# MCU_Board_V1_1_0.net
KiCad netlist of a schematic drawn in EAGLE
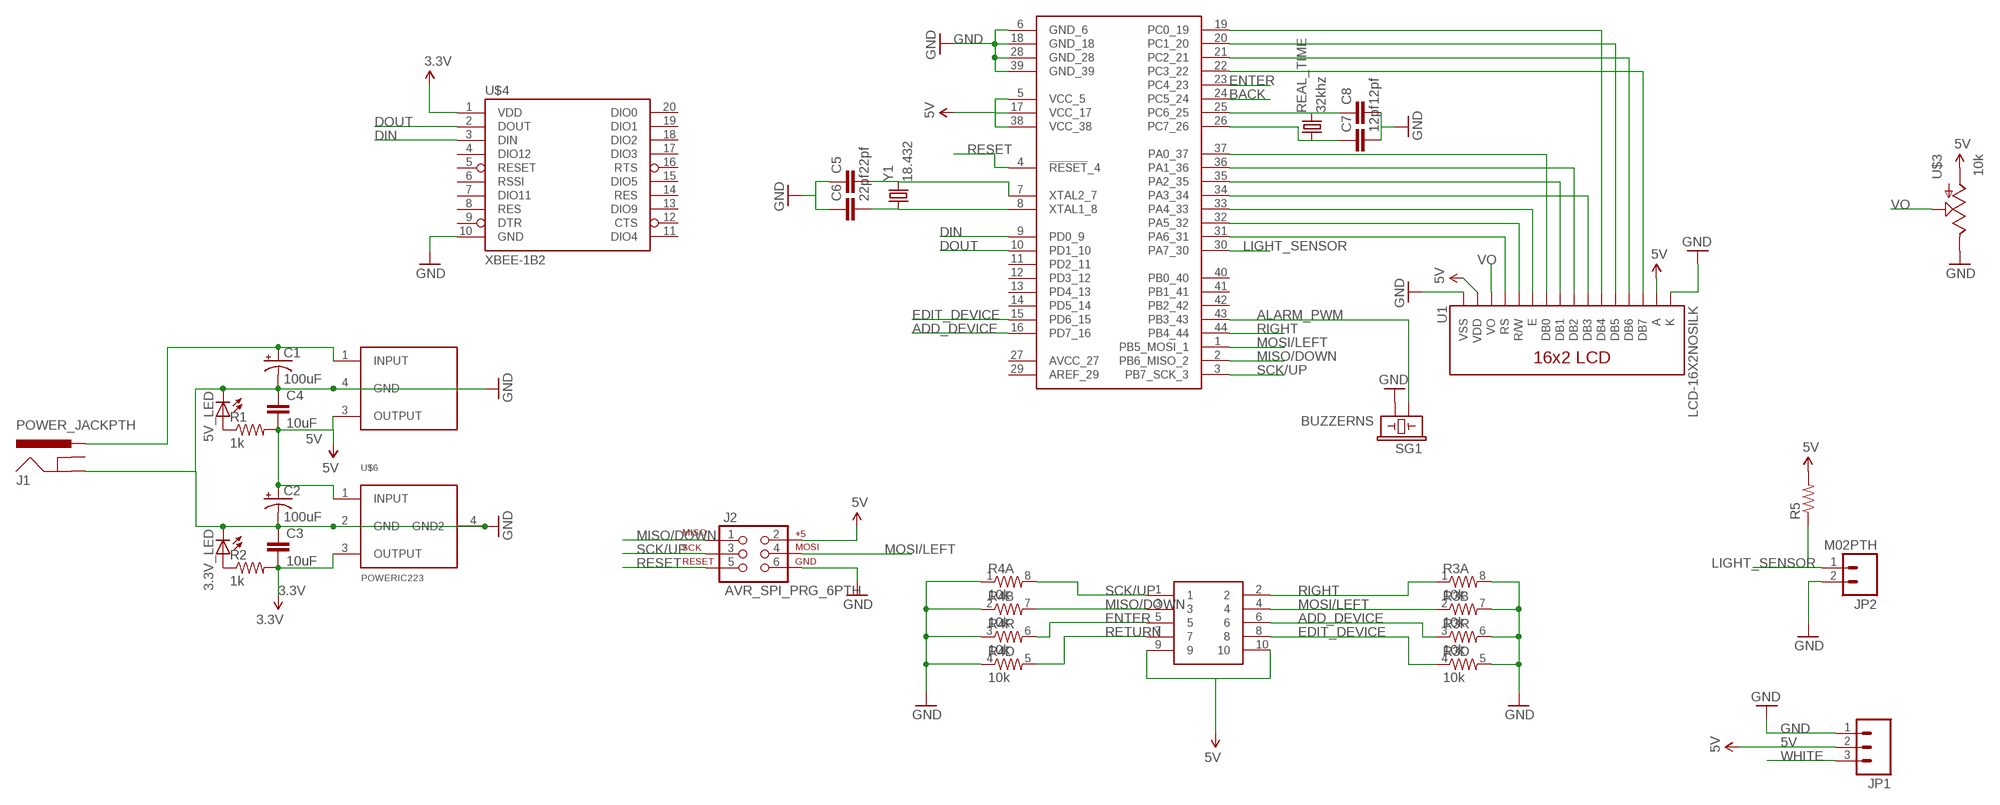
[diagram p0: schematic, sheet 1]

(export (version "E")
  (design (tool "Eeschema 10.0.6"))
  (components
    (comp (ref "3.3V_LED")
      (value "LED1206")
      (footprint "eagle-import:LED-1206")
      (libsource (lib "eagle-import") (part "LED1206"))
    )
    (comp (ref "5V_LED")
      (value "LED1206")
      (footprint "eagle-import:LED-1206")
      (libsource (lib "eagle-import") (part "LED1206"))
    )
    (comp (ref "C1")
      (value "100uF")
      (footprint "eagle-import:PANASONIC_D")
      (libsource (lib "eagle-import") (part "CAP_POLD"))
    )
    (comp (ref "C2")
      (value "100uF")
      (footprint "eagle-import:PANASONIC_D")
      (libsource (lib "eagle-import") (part "CAP_POLD"))
    )
    (comp (ref "C3")
      (value "10uF")
      (footprint "eagle-import:1206")
      (libsource (lib "eagle-import") (part "CAP1206"))
    )
    (comp (ref "C4")
      (value "10uF")
      (footprint "eagle-import:1206")
      (libsource (lib "eagle-import") (part "CAP1206"))
    )
    (comp (ref "C5")
      (value "22pf")
      (footprint "eagle-import:0805")
      (libsource (lib "eagle-import") (part "CAP0805"))
    )
    (comp (ref "C6")
      (value "22pf")
      (footprint "eagle-import:0805")
      (libsource (lib "eagle-import") (part "CAP0805"))
    )
    (comp (ref "C7")
      (value "12pf")
      (footprint "eagle-import:0805")
      (libsource (lib "eagle-import") (part "SparkFun-Passives_CAP0805"))
    )
    (comp (ref "C8")
      (value "12pf")
      (footprint "eagle-import:0805")
      (libsource (lib "eagle-import") (part "SparkFun-Passives_CAP0805"))
    )
    (comp (ref "J1")
      (value "POWER_JACKPTH")
      (footprint "eagle-import:POWER_JACK_PTH")
      (libsource (lib "eagle-import") (part "POWER_JACKPTH"))
    )
    (comp (ref "J2")
      (value "AVR_SPI_PRG_6PTH")
      (footprint "eagle-import:2X3")
      (libsource (lib "eagle-import") (part "AVR_SPI_PRG_6PTH"))
    )
    (comp (ref "JP1")
      (value "M03PTH")
      (footprint "eagle-import:1X03")
      (libsource (lib "eagle-import") (part "M03PTH"))
    )
    (comp (ref "JP2")
      (value "M02PTH")
      (footprint "eagle-import:1X02")
      (libsource (lib "eagle-import") (part "M02PTH"))
    )
    (comp (ref "R1")
      (value "1k")
      (footprint "eagle-import:1206")
      (libsource (lib "eagle-import") (part "RESISTOR1206"))
    )
    (comp (ref "R2")
      (value "1k")
      (footprint "eagle-import:1206")
      (libsource (lib "eagle-import") (part "RESISTOR1206"))
    )
    (comp (ref "R3")
      (value "10k")
      (footprint "eagle-import:0603-ARV")
      (libsource (lib "eagle-import") (part "RESISTOR-ARRAY0603-ARV"))
    )
    (comp (ref "R4")
      (value "10k")
      (footprint "eagle-import:0603-ARV")
      (libsource (lib "eagle-import") (part "RESISTOR-ARRAY0603-ARV"))
    )
    (comp (ref "R5")
      (value "RESISTOR1206")
      (footprint "eagle-import:1206")
      (libsource (lib "eagle-import") (part "RESISTOR1206"))
    )
    (comp (ref "REAL_TIME")
      (value "32khz")
      (footprint "eagle-import:TC26H")
      (libsource (lib "eagle-import") (part "CRYSTALTC26H"))
    )
    (comp (ref "SG1")
      (value "BUZZERNS")
      (footprint "eagle-import:BUZZER-12MM-NS")
      (libsource (lib "eagle-import") (part "BUZZERNS"))
    )
    (comp (ref "U$1")
      (value "ATMEGA1284")
      (footprint "eagle-import:TQFP44")
      (libsource (lib "eagle-import") (part "ATMEGA1284"))
    )
    (comp (ref "U$2")
      (value "10PIN_HEADER_MALETHROUGH-HOLE")
      (footprint "eagle-import:2X5-SHROUDED")
      (libsource (lib "eagle-import") (part "10PIN_HEADER_MALETHROUGH-HOLE"))
    )
    (comp (ref "U$3")
      (value "10k")
      (footprint "eagle-import:TRIM_POT")
      (libsource (lib "eagle-import") (part "POTTRIM"))
    )
    (comp (ref "U$4")
      (value "XBEE-1B2")
      (footprint "eagle-import:XBEE-SILK")
      (libsource (lib "eagle-import") (part "XBEE-1B2"))
    )
    (comp (ref "U$5")
      (value "DPACK_V_REG")
      (footprint "eagle-import:DPAK")
      (libsource (lib "eagle-import") (part "DPACK_V_REG"))
    )
    (comp (ref "U$6")
      (value "POWERIC223")
      (footprint "eagle-import:SOT223")
      (libsource (lib "eagle-import") (part "POWERIC223"))
    )
    (comp (ref "U1")
      (value "LCD-16X2NOSILK")
      (footprint "eagle-import:LCD-16X2_NOSILK")
      (libsource (lib "eagle-import") (part "LCD-16X2NOSILK"))
    )
    (comp (ref "Y1")
      (value "18.432")
      (footprint "eagle-import:HC49US")
      (libsource (lib "eagle-import") (part "CRYSTALHC49US"))
    )
  )
  (nets
    (net (code "1") (name "/ADD_DEVICE") (class "Default")
      (node (ref "R3") (pin "3") (pinfunction "1_3") (pintype "passive"))
      (node (ref "U$1") (pin "16") (pinfunction "PD7_16_16") (pintype "bidirectional"))
      (node (ref "U$2") (pin "6") (pinfunction "6_6") (pintype "bidirectional"))
    )
    (net (code "2") (name "/ALARM_PWM") (class "Default")
      (node (ref "SG1") (pin "+") (pinfunction "1_+") (pintype "passive"))
      (node (ref "U$1") (pin "43") (pinfunction "PB3_43_43") (pintype "bidirectional"))
    )
    (net (code "3") (name "/BACK") (class "Default")
      (node (ref "U$1") (pin "24") (pinfunction "PC5_24_24") (pintype "bidirectional"))
    )
    (net (code "4") (name "/DIN") (class "Default")
      (node (ref "U$1") (pin "9") (pinfunction "PD0_9_9") (pintype "bidirectional"))
      (node (ref "U$4") (pin "3") (pinfunction "DIN_3") (pintype "input"))
    )
    (net (code "5") (name "/DOUT") (class "Default")
      (node (ref "U$1") (pin "10") (pinfunction "PD1_10_10") (pintype "bidirectional"))
      (node (ref "U$4") (pin "2") (pinfunction "DOUT_2") (pintype "output"))
    )
    (net (code "6") (name "/EDIT_DEVICE") (class "Default")
      (node (ref "R3") (pin "4") (pinfunction "1_4") (pintype "passive"))
      (node (ref "U$1") (pin "15") (pinfunction "PD6_15_15") (pintype "bidirectional"))
      (node (ref "U$2") (pin "8") (pinfunction "8_8") (pintype "bidirectional"))
    )
    (net (code "7") (name "/ENTER") (class "Default")
      (node (ref "R4") (pin "6") (pinfunction "2_6") (pintype "passive"))
      (node (ref "U$1") (pin "23") (pinfunction "PC4_23_23") (pintype "bidirectional"))
      (node (ref "U$2") (pin "5") (pinfunction "5_5") (pintype "bidirectional"))
    )
    (net (code "8") (name "/LIGHT_SENSOR") (class "Default")
      (node (ref "JP2") (pin "1") (pinfunction "1_1") (pintype "passive"))
      (node (ref "R5") (pin "1") (pinfunction "1_1") (pintype "passive"))
      (node (ref "U$1") (pin "30") (pinfunction "PA7_30_30") (pintype "bidirectional"))
    )
    (net (code "9") (name "/MISO{slash}DOWN") (class "Default")
      (node (ref "J2") (pin "1") (pinfunction "1_1") (pintype "passive"))
      (node (ref "R4") (pin "7") (pinfunction "2_7") (pintype "passive"))
      (node (ref "U$1") (pin "2") (pinfunction "PB6_MISO_2_2") (pintype "bidirectional"))
      (node (ref "U$2") (pin "3") (pinfunction "3_3") (pintype "bidirectional"))
    )
    (net (code "10") (name "/MOSI{slash}LEFT") (class "Default")
      (node (ref "J2") (pin "4") (pinfunction "4_4") (pintype "passive"))
      (node (ref "R3") (pin "2") (pinfunction "1_2") (pintype "passive"))
      (node (ref "U$1") (pin "1") (pinfunction "PB5_MOSI_1_1") (pintype "bidirectional"))
      (node (ref "U$2") (pin "4") (pinfunction "4_4") (pintype "bidirectional"))
    )
    (net (code "11") (name "/RESET") (class "Default")
      (node (ref "J2") (pin "5") (pinfunction "5_5") (pintype "passive"))
      (node (ref "U$1") (pin "4") (pinfunction "~{RESET}_4_4") (pintype "bidirectional"))
    )
    (net (code "12") (name "/RETURN") (class "Default")
      (node (ref "R4") (pin "5") (pinfunction "2_5") (pintype "passive"))
      (node (ref "U$2") (pin "7") (pinfunction "7_7") (pintype "bidirectional"))
    )
    (net (code "13") (name "/RIGHT") (class "Default")
      (node (ref "R3") (pin "1") (pinfunction "1_1") (pintype "passive"))
      (node (ref "U$1") (pin "44") (pinfunction "PB4_44_44") (pintype "bidirectional"))
      (node (ref "U$2") (pin "2") (pinfunction "2_2") (pintype "bidirectional"))
    )
    (net (code "14") (name "/SCK{slash}UP") (class "Default")
      (node (ref "J2") (pin "3") (pinfunction "3_3") (pintype "passive"))
      (node (ref "R4") (pin "8") (pinfunction "2_8") (pintype "passive"))
      (node (ref "U$1") (pin "3") (pinfunction "PB7_SCK_3_3") (pintype "bidirectional"))
      (node (ref "U$2") (pin "1") (pinfunction "1_1") (pintype "bidirectional"))
    )
    (net (code "15") (name "/VO") (class "Default")
      (node (ref "U$3") (pin "1") (pinfunction "S_1") (pintype "passive"))
      (node (ref "U1") (pin "3") (pinfunction "VO_3") (pintype "bidirectional"))
    )
    (net (code "16") (name "/WHITE") (class "Default")
      (node (ref "JP1") (pin "3") (pinfunction "3_3") (pintype "passive"))
    )
    (net (code "17") (name "3.3V") (class "Default")
      (node (ref "C3") (pin "2") (pinfunction "2_2") (pintype "passive"))
      (node (ref "R2") (pin "2") (pinfunction "2_2") (pintype "passive"))
      (node (ref "U$4") (pin "1") (pinfunction "VDD_1") (pintype "power_in"))
      (node (ref "U$6") (pin "3") (pinfunction "OUTPUT_3") (pintype "bidirectional"))
    )
    (net (code "18") (name "5V") (class "Default")
      (node (ref "C2") (pin "+") (pinfunction "+_+") (pintype "passive"))
      (node (ref "C4") (pin "2") (pinfunction "2_2") (pintype "passive"))
      (node (ref "J2") (pin "2") (pinfunction "2_2") (pintype "passive"))
      (node (ref "JP1") (pin "2") (pinfunction "2_2") (pintype "passive"))
      (node (ref "R1") (pin "2") (pinfunction "2_2") (pintype "passive"))
      (node (ref "R5") (pin "2") (pinfunction "2_2") (pintype "passive"))
      (node (ref "U$1") (pin "17") (pinfunction "VCC_17_17") (pintype "bidirectional"))
      (node (ref "U$1") (pin "38") (pinfunction "VCC_38_38") (pintype "bidirectional"))
      (node (ref "U$1") (pin "5") (pinfunction "VCC_5_5") (pintype "bidirectional"))
      (node (ref "U$2") (pin "10") (pinfunction "10_10") (pintype "bidirectional"))
      (node (ref "U$2") (pin "9") (pinfunction "9_9") (pintype "bidirectional"))
      (node (ref "U$3") (pin "3") (pinfunction "A_3") (pintype "passive"))
      (node (ref "U$5") (pin "3") (pinfunction "OUTPUT_3") (pintype "bidirectional"))
      (node (ref "U$6") (pin "1") (pinfunction "INPUT_1") (pintype "bidirectional"))
      (node (ref "U1") (pin "15") (pinfunction "A_15") (pintype "power_in"))
      (node (ref "U1") (pin "2") (pinfunction "VDD_2") (pintype "power_in"))
    )
    (net (code "19") (name "GND") (class "Default")
      (node (ref "3.3V_LED") (pin "C") (pinfunction "C_C") (pintype "passive"))
      (node (ref "5V_LED") (pin "C") (pinfunction "C_C") (pintype "passive"))
      (node (ref "C1") (pin "-") (pinfunction "-_-") (pintype "passive"))
      (node (ref "C2") (pin "-") (pinfunction "-_-") (pintype "passive"))
      (node (ref "C3") (pin "1") (pinfunction "1_1") (pintype "passive"))
      (node (ref "C4") (pin "1") (pinfunction "1_1") (pintype "passive"))
      (node (ref "C5") (pin "1") (pinfunction "1_1") (pintype "passive"))
      (node (ref "C6") (pin "1") (pinfunction "1_1") (pintype "passive"))
      (node (ref "C7") (pin "2") (pinfunction "2_2") (pintype "passive"))
      (node (ref "C8") (pin "2") (pinfunction "2_2") (pintype "passive"))
      (node (ref "J1") (pin "GND") (pinfunction "GND_GND") (pintype "bidirectional"))
      (node (ref "J2") (pin "6") (pinfunction "6_6") (pintype "passive"))
      (node (ref "JP1") (pin "1") (pinfunction "1_1") (pintype "passive"))
      (node (ref "JP2") (pin "2") (pinfunction "2_2") (pintype "passive"))
      (node (ref "R3") (pin "5") (pinfunction "2_5") (pintype "passive"))
      (node (ref "R3") (pin "6") (pinfunction "2_6") (pintype "passive"))
      (node (ref "R3") (pin "7") (pinfunction "2_7") (pintype "passive"))
      (node (ref "R3") (pin "8") (pinfunction "2_8") (pintype "passive"))
      (node (ref "R4") (pin "1") (pinfunction "1_1") (pintype "passive"))
      (node (ref "R4") (pin "2") (pinfunction "1_2") (pintype "passive"))
      (node (ref "R4") (pin "3") (pinfunction "1_3") (pintype "passive"))
      (node (ref "R4") (pin "4") (pinfunction "1_4") (pintype "passive"))
      (node (ref "SG1") (pin "-") (pinfunction "2_-") (pintype "passive"))
      (node (ref "U$1") (pin "18") (pinfunction "GND_18_18") (pintype "bidirectional"))
      (node (ref "U$1") (pin "28") (pinfunction "GND_28_28") (pintype "bidirectional"))
      (node (ref "U$1") (pin "39") (pinfunction "GND_39_39") (pintype "bidirectional"))
      (node (ref "U$1") (pin "6") (pinfunction "GND_6_6") (pintype "bidirectional"))
      (node (ref "U$3") (pin "2") (pinfunction "E_2") (pintype "passive"))
      (node (ref "U$4") (pin "10") (pinfunction "GND_10") (pintype "power_in"))
      (node (ref "U$5") (pin "4") (pinfunction "GND_4") (pintype "bidirectional"))
      (node (ref "U$6") (pin "2") (pinfunction "GND_2") (pintype "bidirectional"))
      (node (ref "U$6") (pin "4") (pinfunction "GND2_4") (pintype "bidirectional"))
      (node (ref "U1") (pin "1") (pinfunction "VSS_1") (pintype "power_in"))
      (node (ref "U1") (pin "16") (pinfunction "K_16") (pintype "power_in"))
    )
    (net (code "20") (name "Net-(3.3V_LED-PadA)") (class "Default")
      (node (ref "3.3V_LED") (pin "A") (pinfunction "A_A") (pintype "passive"))
      (node (ref "R2") (pin "1") (pinfunction "1_1") (pintype "passive"))
    )
    (net (code "21") (name "Net-(5V_LED-PadA)") (class "Default")
      (node (ref "5V_LED") (pin "A") (pinfunction "A_A") (pintype "passive"))
      (node (ref "R1") (pin "1") (pinfunction "1_1") (pintype "passive"))
    )
    (net (code "22") (name "Net-(U$1-PA0_37)") (class "Default")
      (node (ref "U$1") (pin "37") (pinfunction "PA0_37_37") (pintype "bidirectional"))
      (node (ref "U1") (pin "7") (pinfunction "DB0_7") (pintype "bidirectional"))
    )
    (net (code "23") (name "Net-(U$1-PA1_36)") (class "Default")
      (node (ref "U$1") (pin "36") (pinfunction "PA1_36_36") (pintype "bidirectional"))
      (node (ref "U1") (pin "9") (pinfunction "DB2_9") (pintype "bidirectional"))
    )
    (net (code "24") (name "Net-(U$1-PA2_35)") (class "Default")
      (node (ref "U$1") (pin "35") (pinfunction "PA2_35_35") (pintype "bidirectional"))
      (node (ref "U1") (pin "8") (pinfunction "DB1_8") (pintype "bidirectional"))
    )
    (net (code "25") (name "Net-(U$1-PA3_34)") (class "Default")
      (node (ref "U$1") (pin "34") (pinfunction "PA3_34_34") (pintype "bidirectional"))
      (node (ref "U1") (pin "10") (pinfunction "DB3_10") (pintype "bidirectional"))
    )
    (net (code "26") (name "Net-(U$1-PA4_33)") (class "Default")
      (node (ref "U$1") (pin "33") (pinfunction "PA4_33_33") (pintype "bidirectional"))
      (node (ref "U1") (pin "6") (pinfunction "E_6") (pintype "input"))
    )
    (net (code "27") (name "Net-(U$1-PA5_32)") (class "Default")
      (node (ref "U$1") (pin "32") (pinfunction "PA5_32_32") (pintype "bidirectional"))
      (node (ref "U1") (pin "5") (pinfunction "R/W_5") (pintype "input"))
    )
    (net (code "28") (name "Net-(U$1-PA6_31)") (class "Default")
      (node (ref "U$1") (pin "31") (pinfunction "PA6_31_31") (pintype "bidirectional"))
      (node (ref "U1") (pin "4") (pinfunction "RS_4") (pintype "input"))
    )
    (net (code "29") (name "Net-(U$1-PC0_19)") (class "Default")
      (node (ref "U$1") (pin "19") (pinfunction "PC0_19_19") (pintype "bidirectional"))
      (node (ref "U1") (pin "11") (pinfunction "DB4_11") (pintype "bidirectional"))
    )
    (net (code "30") (name "Net-(U$1-PC1_20)") (class "Default")
      (node (ref "U$1") (pin "20") (pinfunction "PC1_20_20") (pintype "bidirectional"))
      (node (ref "U1") (pin "12") (pinfunction "DB5_12") (pintype "bidirectional"))
    )
    (net (code "31") (name "Net-(U$1-PC2_21)") (class "Default")
      (node (ref "U$1") (pin "21") (pinfunction "PC2_21_21") (pintype "bidirectional"))
      (node (ref "U1") (pin "13") (pinfunction "DB6_13") (pintype "bidirectional"))
    )
    (net (code "32") (name "Net-(U$1-PC3_22)") (class "Default")
      (node (ref "U$1") (pin "22") (pinfunction "PC3_22_22") (pintype "bidirectional"))
      (node (ref "U1") (pin "14") (pinfunction "DB7_14") (pintype "bidirectional"))
    )
    (net (code "33") (name "Net-(U$1-PC6_25)") (class "Default")
      (node (ref "C8") (pin "1") (pinfunction "1_1") (pintype "passive"))
      (node (ref "REAL_TIME") (pin "2") (pinfunction "2_2") (pintype "passive"))
      (node (ref "U$1") (pin "25") (pinfunction "PC6_25_25") (pintype "bidirectional"))
    )
    (net (code "34") (name "Net-(U$1-PC7_26)") (class "Default")
      (node (ref "C7") (pin "1") (pinfunction "1_1") (pintype "passive"))
      (node (ref "REAL_TIME") (pin "1") (pinfunction "1_1") (pintype "passive"))
      (node (ref "U$1") (pin "26") (pinfunction "PC7_26_26") (pintype "bidirectional"))
    )
    (net (code "35") (name "Net-(U$1-XTAL1_8)") (class "Default")
      (node (ref "C6") (pin "2") (pinfunction "2_2") (pintype "passive"))
      (node (ref "U$1") (pin "8") (pinfunction "XTAL1_8_8") (pintype "bidirectional"))
      (node (ref "Y1") (pin "1") (pinfunction "1_1") (pintype "passive"))
    )
    (net (code "36") (name "Net-(U$1-XTAL2_7)") (class "Default")
      (node (ref "C5") (pin "2") (pinfunction "2_2") (pintype "passive"))
      (node (ref "U$1") (pin "7") (pinfunction "XTAL2_7_7") (pintype "bidirectional"))
      (node (ref "Y1") (pin "2") (pinfunction "2_2") (pintype "passive"))
    )
    (net (code "37") (name "Net-(U$5-INPUT)") (class "Default")
      (node (ref "C1") (pin "+") (pinfunction "+_+") (pintype "passive"))
      (node (ref "J1") (pin "PWR") (pinfunction "PWR_PWR") (pintype "bidirectional"))
      (node (ref "U$5") (pin "1") (pinfunction "INPUT_1") (pintype "bidirectional"))
    )
    (net (code "38") (name "unconnected-(J1-PadGNDBREAK)") (class "Default")
      (node (ref "J1") (pin "GNDBREAK") (pinfunction "GNDBREAK_GNDBREAK") (pintype "bidirectional"))
    )
    (net (code "39") (name "unconnected-(U$1-AREF_29-Pad29)") (class "Default")
      (node (ref "U$1") (pin "29") (pinfunction "AREF_29_29") (pintype "bidirectional"))
    )
    (net (code "40") (name "unconnected-(U$1-AVCC_27-Pad27)") (class "Default")
      (node (ref "U$1") (pin "27") (pinfunction "AVCC_27_27") (pintype "bidirectional"))
    )
    (net (code "41") (name "unconnected-(U$1-PB0_40-Pad40)") (class "Default")
      (node (ref "U$1") (pin "40") (pinfunction "PB0_40_40") (pintype "bidirectional"))
    )
    (net (code "42") (name "unconnected-(U$1-PB1_41-Pad41)") (class "Default")
      (node (ref "U$1") (pin "41") (pinfunction "PB1_41_41") (pintype "bidirectional"))
    )
    (net (code "43") (name "unconnected-(U$1-PB2_42-Pad42)") (class "Default")
      (node (ref "U$1") (pin "42") (pinfunction "PB2_42_42") (pintype "bidirectional"))
    )
    (net (code "44") (name "unconnected-(U$1-PD2_11-Pad11)") (class "Default")
      (node (ref "U$1") (pin "11") (pinfunction "PD2_11_11") (pintype "bidirectional"))
    )
    (net (code "45") (name "unconnected-(U$1-PD3_12-Pad12)") (class "Default")
      (node (ref "U$1") (pin "12") (pinfunction "PD3_12_12") (pintype "bidirectional"))
    )
    (net (code "46") (name "unconnected-(U$1-PD4_13-Pad13)") (class "Default")
      (node (ref "U$1") (pin "13") (pinfunction "PD4_13_13") (pintype "bidirectional"))
    )
    (net (code "47") (name "unconnected-(U$1-PD5_14-Pad14)") (class "Default")
      (node (ref "U$1") (pin "14") (pinfunction "PD5_14_14") (pintype "bidirectional"))
    )
    (net (code "48") (name "unconnected-(U$4-CTS-Pad12)") (class "Default")
      (node (ref "U$4") (pin "12") (pinfunction "CTS_12") (pintype "output"))
    )
    (net (code "49") (name "unconnected-(U$4-DIO0-Pad20)") (class "Default")
      (node (ref "U$4") (pin "20") (pinfunction "DIO0_20") (pintype "bidirectional"))
    )
    (net (code "50") (name "unconnected-(U$4-DIO1-Pad19)") (class "Default")
      (node (ref "U$4") (pin "19") (pinfunction "DIO1_19") (pintype "bidirectional"))
    )
    (net (code "51") (name "unconnected-(U$4-DIO2-Pad18)") (class "Default")
      (node (ref "U$4") (pin "18") (pinfunction "DIO2_18") (pintype "bidirectional"))
    )
    (net (code "52") (name "unconnected-(U$4-DIO3-Pad17)") (class "Default")
      (node (ref "U$4") (pin "17") (pinfunction "DIO3_17") (pintype "bidirectional"))
    )
    (net (code "53") (name "unconnected-(U$4-DIO4-Pad11)") (class "Default")
      (node (ref "U$4") (pin "11") (pinfunction "DIO4_11") (pintype "bidirectional"))
    )
    (net (code "54") (name "unconnected-(U$4-DIO5-Pad15)") (class "Default")
      (node (ref "U$4") (pin "15") (pinfunction "DIO5_15") (pintype "bidirectional"))
    )
    (net (code "55") (name "unconnected-(U$4-DIO9-Pad13)") (class "Default")
      (node (ref "U$4") (pin "13") (pinfunction "DIO9_13") (pintype "bidirectional"))
    )
    (net (code "56") (name "unconnected-(U$4-DIO11-Pad7)") (class "Default")
      (node (ref "U$4") (pin "7") (pinfunction "DIO11_7") (pintype "bidirectional"))
    )
    (net (code "57") (name "unconnected-(U$4-DIO12-Pad4)") (class "Default")
      (node (ref "U$4") (pin "4") (pinfunction "DIO12_4") (pintype "bidirectional"))
    )
    (net (code "58") (name "unconnected-(U$4-DTR-Pad9)") (class "Default")
      (node (ref "U$4") (pin "9") (pinfunction "DTR_9") (pintype "bidirectional"))
    )
    (net (code "59") (name "unconnected-(U$4-RES-Pad8)") (class "Default")
      (node (ref "U$4") (pin "8") (pinfunction "RES_8") (pintype "bidirectional"))
    )
    (net (code "60") (name "unconnected-(U$4-RES-Pad14)") (class "Default")
      (node (ref "U$4") (pin "14") (pinfunction "RES_14") (pintype "bidirectional"))
    )
    (net (code "61") (name "unconnected-(U$4-RESET-Pad5)") (class "Default")
      (node (ref "U$4") (pin "5") (pinfunction "RESET_5") (pintype "input"))
    )
    (net (code "62") (name "unconnected-(U$4-RSSI-Pad6)") (class "Default")
      (node (ref "U$4") (pin "6") (pinfunction "RSSI_6") (pintype "bidirectional"))
    )
    (net (code "63") (name "unconnected-(U$4-RTS-Pad16)") (class "Default")
      (node (ref "U$4") (pin "16") (pinfunction "RTS_16") (pintype "input"))
    )
  )
)
